# Schaltplan.net
KiCad netlist of a schematic drawn in EAGLE
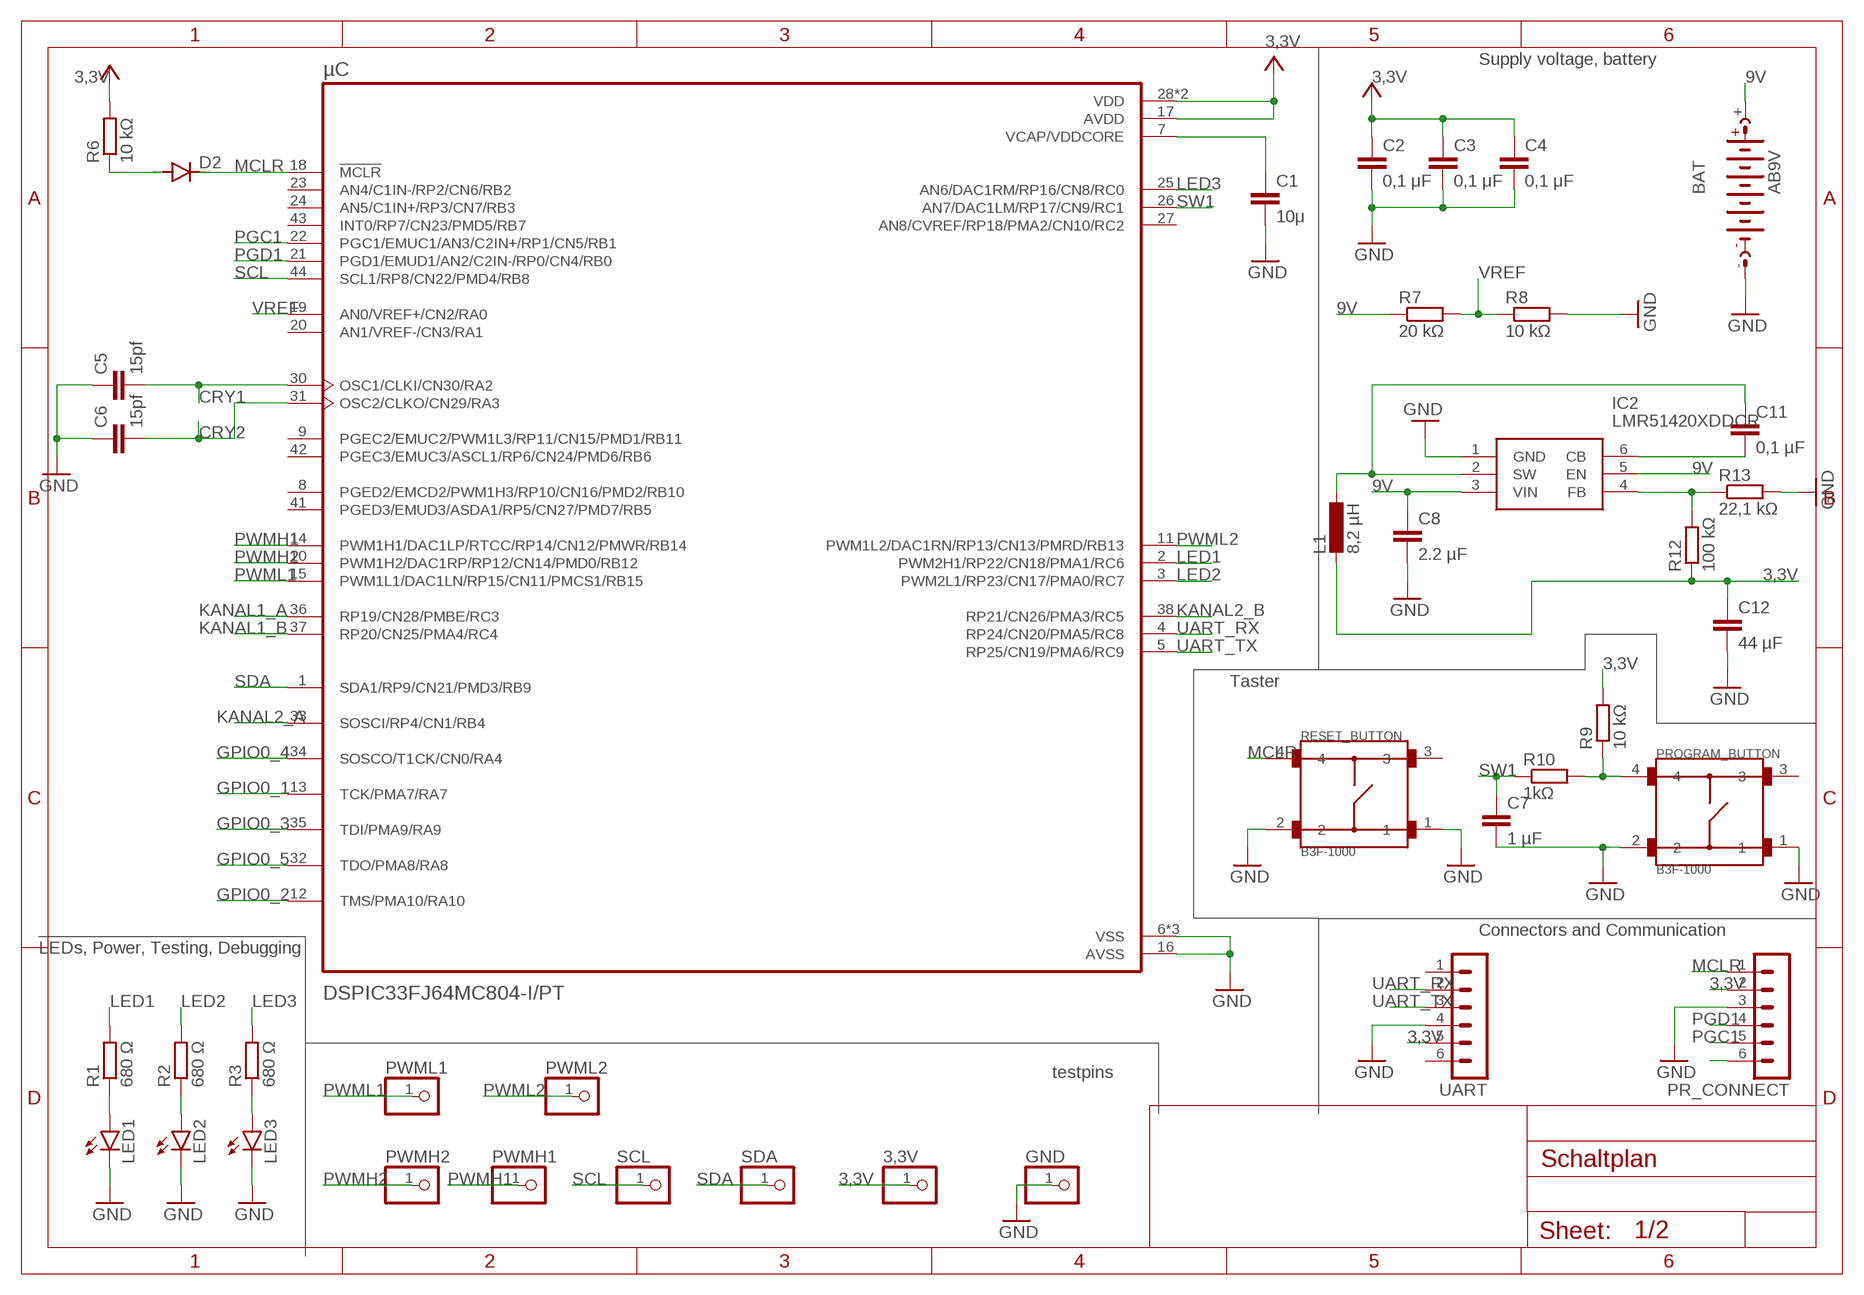
[diagram p0: schematic, sheet 1]
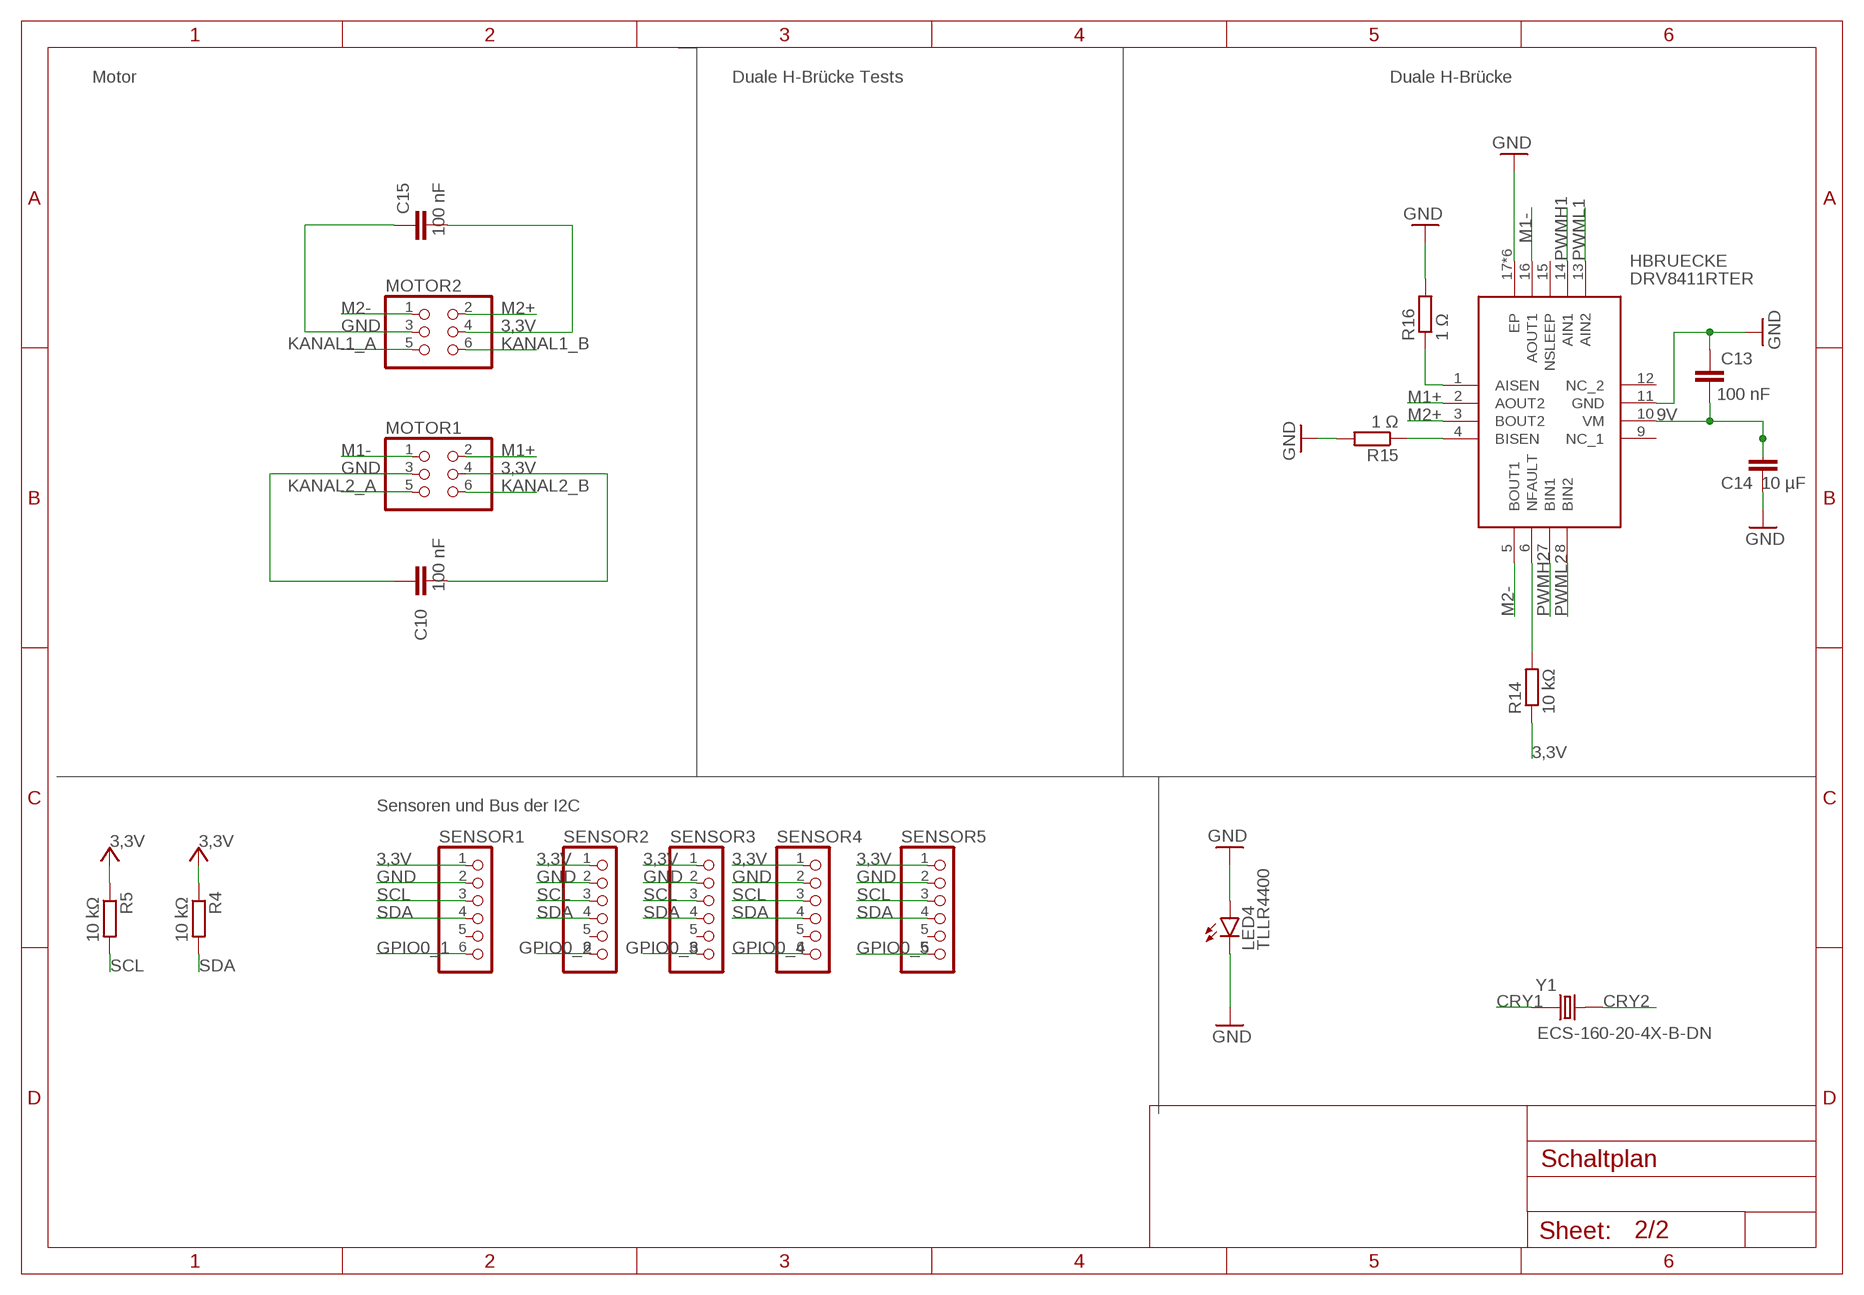
[diagram p1: schematic, sheet 2]

(export (version "E")
  (design (tool "Eeschema 10.0.6"))
  (components
    (comp (ref "3,3V")
      (value "PINHD-1X1")
      (footprint "eagle-import:1X01")
      (libsource (lib "eagle-import") (part "PINHD-1X1"))
    )
    (comp (ref "BAT")
      (value "AB9V")
      (footprint "eagle-import:AB9V")
      (libsource (lib "eagle-import") (part "AB9V"))
    )
    (comp (ref "C1")
      (value "10μ")
      (footprint "eagle-import:C0805")
      (libsource (lib "eagle-import") (part "C-EUC0805"))
    )
    (comp (ref "C2")
      (value "0,1 μF")
      (footprint "eagle-import:C0805")
      (libsource (lib "eagle-import") (part "C-EUC0805"))
    )
    (comp (ref "C3")
      (value "0,1 μF")
      (footprint "eagle-import:C0805")
      (libsource (lib "eagle-import") (part "C-EUC0805"))
    )
    (comp (ref "C4")
      (value "0,1 μF")
      (footprint "eagle-import:C0805")
      (libsource (lib "eagle-import") (part "C-EUC0805"))
    )
    (comp (ref "C5")
      (value "15pf")
      (footprint "eagle-import:C0805")
      (libsource (lib "eagle-import") (part "C-EUC0805"))
    )
    (comp (ref "C6")
      (value "15pf")
      (footprint "eagle-import:C0805")
      (libsource (lib "eagle-import") (part "C-EUC0805"))
    )
    (comp (ref "C7")
      (value "1 µF")
      (footprint "eagle-import:C0805")
      (libsource (lib "eagle-import") (part "C-EUC0805"))
    )
    (comp (ref "C8")
      (value "2.2 µF")
      (footprint "eagle-import:C0805")
      (libsource (lib "eagle-import") (part "C-EUC0805"))
    )
    (comp (ref "C11")
      (value "0,1 µF")
      (footprint "eagle-import:C0805")
      (libsource (lib "eagle-import") (part "C-EUC0805"))
    )
    (comp (ref "C12")
      (value "44 µF")
      (footprint "eagle-import:C0805")
      (libsource (lib "eagle-import") (part "C-EUC0805"))
    )
    (comp (ref "D2")
      (value "DIODE-DO-214AC")
      (footprint "eagle-import:DO-214AC")
      (libsource (lib "eagle-import") (part "DIODE-DO-214AC"))
    )
    (comp (ref "GND")
      (value "PINHD-1X1")
      (footprint "eagle-import:1X01")
      (libsource (lib "eagle-import") (part "PINHD-1X1"))
    )
    (comp (ref "IC2")
      (value "LMR51420XDDCR")
      (footprint "eagle-import:SOT95P280X110-6N")
      (fields (field (name "MOUSER_PART_NUMBER") "595-LMR51420XDDCR"))
      (libsource (lib "eagle-import") (part "LMR51420XDDCR"))
    )
    (comp (ref "L1")
      (value "8,2 µH")
      (footprint "eagle-import:L0201")
      (libsource (lib "eagle-import") (part "L-EUL0201"))
    )
    (comp (ref "LED1")
      (value "LEDCHIPLED_0805")
      (footprint "eagle-import:CHIPLED_0805")
      (libsource (lib "eagle-import") (part "LEDCHIPLED_0805"))
    )
    (comp (ref "LED2")
      (value "LEDCHIPLED_0805")
      (footprint "eagle-import:CHIPLED_0805")
      (libsource (lib "eagle-import") (part "LEDCHIPLED_0805"))
    )
    (comp (ref "LED3")
      (value "LEDCHIPLED_0805")
      (footprint "eagle-import:CHIPLED_0805")
      (libsource (lib "eagle-import") (part "LEDCHIPLED_0805"))
    )
    (comp (ref "PROGRAM_BUTTON")
      (value "B3F-1000")
      (footprint "eagle-import:SW_B3F-1000")
      (fields (field (name "MF") "Omron"))
      (libsource (lib "eagle-import") (part "B3F-1000"))
    )
    (comp (ref "PR_CONNECT")
      (value "MA06-1")
      (footprint "eagle-import:MA06-1")
      (libsource (lib "eagle-import") (part "MA06-1"))
    )
    (comp (ref "PWMH1")
      (value "PINHD-1X1")
      (footprint "eagle-import:1X01")
      (libsource (lib "eagle-import") (part "PINHD-1X1"))
    )
    (comp (ref "PWMH2")
      (value "PINHD-1X1")
      (footprint "eagle-import:1X01")
      (libsource (lib "eagle-import") (part "PINHD-1X1"))
    )
    (comp (ref "PWML1")
      (value "PINHD-1X1")
      (footprint "eagle-import:1X01")
      (libsource (lib "eagle-import") (part "PINHD-1X1"))
    )
    (comp (ref "PWML2")
      (value "PINHD-1X1")
      (footprint "eagle-import:1X01")
      (libsource (lib "eagle-import") (part "PINHD-1X1"))
    )
    (comp (ref "R1")
      (value "680 Ω")
      (footprint "eagle-import:R0805")
      (libsource (lib "eagle-import") (part "R-EU_R0805"))
    )
    (comp (ref "R2")
      (value "680 Ω")
      (footprint "eagle-import:R0805")
      (libsource (lib "eagle-import") (part "R-EU_R0805"))
    )
    (comp (ref "R3")
      (value "680 Ω")
      (footprint "eagle-import:R0805")
      (libsource (lib "eagle-import") (part "R-EU_R0805"))
    )
    (comp (ref "R6")
      (value "10 kΩ")
      (footprint "eagle-import:R0805")
      (libsource (lib "eagle-import") (part "R-EU_R0805"))
    )
    (comp (ref "R7")
      (value "20 kΩ")
      (footprint "eagle-import:R0805")
      (libsource (lib "eagle-import") (part "R-EU_R0805"))
    )
    (comp (ref "R8")
      (value "10 kΩ")
      (footprint "eagle-import:R0805")
      (libsource (lib "eagle-import") (part "R-EU_R0805"))
    )
    (comp (ref "R9")
      (value "10 kΩ")
      (footprint "eagle-import:R0805")
      (libsource (lib "eagle-import") (part "R-EU_R0805"))
    )
    (comp (ref "R10")
      (value "1kΩ")
      (footprint "eagle-import:R0805")
      (libsource (lib "eagle-import") (part "R-EU_R0805"))
    )
    (comp (ref "R12")
      (value "100 kΩ")
      (footprint "eagle-import:R0805")
      (libsource (lib "eagle-import") (part "R-EU_R0805"))
    )
    (comp (ref "R13")
      (value "22,1 kΩ")
      (footprint "eagle-import:R0805")
      (libsource (lib "eagle-import") (part "R-EU_R0805"))
    )
    (comp (ref "RESET_BUTTON")
      (value "B3F-1000")
      (footprint "eagle-import:SW_B3F-1000")
      (fields (field (name "MF") "Omron"))
      (libsource (lib "eagle-import") (part "B3F-1000"))
    )
    (comp (ref "SCL")
      (value "PINHD-1X1")
      (footprint "eagle-import:1X01")
      (libsource (lib "eagle-import") (part "PINHD-1X1"))
    )
    (comp (ref "SDA")
      (value "PINHD-1X1")
      (footprint "eagle-import:1X01")
      (libsource (lib "eagle-import") (part "PINHD-1X1"))
    )
    (comp (ref "UART")
      (value "MA06-1")
      (footprint "eagle-import:MA06-1")
      (libsource (lib "eagle-import") (part "MA06-1"))
    )
    (comp (ref "µC")
      (value "DSPIC33FJ64MC804-I/PT")
      (footprint "eagle-import:QFP80P1200X1200X120-44N")
      (fields (field (name "MF") "Microchip"))
      (libsource (lib "eagle-import") (part "DSPIC33FJ64MC804-I/PT"))
    )
    (comp (ref "C10")
      (value "100 nF")
      (footprint "eagle-import:C0805")
      (libsource (lib "eagle-import") (part "C-EUC0805"))
    )
    (comp (ref "C13")
      (value "100 nF")
      (footprint "eagle-import:C0805")
      (libsource (lib "eagle-import") (part "C-EUC0805"))
    )
    (comp (ref "C14")
      (value "10 µF")
      (footprint "eagle-import:C0805")
      (libsource (lib "eagle-import") (part "C-EUC0805"))
    )
    (comp (ref "C15")
      (value "100 nF")
      (footprint "eagle-import:C0805")
      (libsource (lib "eagle-import") (part "C-EUC0805"))
    )
    (comp (ref "HBRUECKE")
      (value "DRV8411RTER")
      (footprint "eagle-import:QFN50P300X300X80-17N")
      (libsource (lib "eagle-import") (part "DRV8411RTER"))
    )
    (comp (ref "LED4")
      (value "TLLR4400")
      (footprint "eagle-import:LED3MM")
      (fields (field (name "MF") "VISHAY SEMICONDUCTOR"))
      (libsource (lib "eagle-import") (part "TLLR4400"))
    )
    (comp (ref "MOTOR1")
      (value "PINHD-2X3")
      (footprint "eagle-import:2X03")
      (libsource (lib "eagle-import") (part "PINHD-2X3"))
    )
    (comp (ref "MOTOR2")
      (value "PINHD-2X3")
      (footprint "eagle-import:2X03")
      (libsource (lib "eagle-import") (part "PINHD-2X3"))
    )
    (comp (ref "R4")
      (value "10 kΩ")
      (footprint "eagle-import:R0805")
      (libsource (lib "eagle-import") (part "R-EU_R0805"))
    )
    (comp (ref "R5")
      (value "10 kΩ")
      (footprint "eagle-import:R0805")
      (libsource (lib "eagle-import") (part "R-EU_R0805"))
    )
    (comp (ref "R14")
      (value "10 kΩ")
      (footprint "eagle-import:R0805")
      (libsource (lib "eagle-import") (part "R-EU_R0805"))
    )
    (comp (ref "R15")
      (value "1 Ω")
      (footprint "eagle-import:R0805")
      (libsource (lib "eagle-import") (part "R-EU_R0805"))
    )
    (comp (ref "R16")
      (value "1 Ω")
      (footprint "eagle-import:R0805")
      (libsource (lib "eagle-import") (part "R-EU_R0805"))
    )
    (comp (ref "SENSOR1")
      (value "PINHD-1X6")
      (footprint "eagle-import:1X06")
      (libsource (lib "eagle-import") (part "PINHD-1X6"))
    )
    (comp (ref "SENSOR2")
      (value "PINHD-1X6")
      (footprint "eagle-import:1X06")
      (libsource (lib "eagle-import") (part "PINHD-1X6"))
    )
    (comp (ref "SENSOR3")
      (value "PINHD-1X6")
      (footprint "eagle-import:1X06")
      (libsource (lib "eagle-import") (part "PINHD-1X6"))
    )
    (comp (ref "SENSOR4")
      (value "PINHD-1X6")
      (footprint "eagle-import:1X06")
      (libsource (lib "eagle-import") (part "PINHD-1X6"))
    )
    (comp (ref "SENSOR5")
      (value "PINHD-1X6")
      (footprint "eagle-import:1X06")
      (libsource (lib "eagle-import") (part "PINHD-1X6"))
    )
    (comp (ref "Y1")
      (value "ECS-160-20-4X-B-DN")
      (footprint "eagle-import:XTAL_ECS-160-20-4X-B-DN")
      (fields (field (name "MF") "ECS Inc."))
      (libsource (lib "eagle-import") (part "ECS-160-20-4X-B-DN"))
    )
  )
  (nets
    (net (code "1") (name "3,3V") (class "Default")
      (node (ref "3,3V") (pin "1") (pinfunction "1_1") (pintype "passive"))
      (node (ref "C10") (pin "1") (pinfunction "1_1") (pintype "passive"))
      (node (ref "C12") (pin "1") (pinfunction "1_1") (pintype "passive"))
      (node (ref "C15") (pin "1") (pinfunction "1_1") (pintype "passive"))
      (node (ref "C2") (pin "1") (pinfunction "1_1") (pintype "passive"))
      (node (ref "C3") (pin "1") (pinfunction "1_1") (pintype "passive"))
      (node (ref "C4") (pin "1") (pinfunction "1_1") (pintype "passive"))
      (node (ref "L1") (pin "2") (pinfunction "2_2") (pintype "passive"))
      (node (ref "MOTOR1") (pin "4") (pinfunction "4_4") (pintype "passive"))
      (node (ref "MOTOR2") (pin "4") (pinfunction "4_4") (pintype "passive"))
      (node (ref "PR_CONNECT") (pin "2") (pinfunction "2_2") (pintype "passive"))
      (node (ref "R12") (pin "1") (pinfunction "1_1") (pintype "passive"))
      (node (ref "R14") (pin "1") (pinfunction "1_1") (pintype "passive"))
      (node (ref "R4") (pin "1") (pinfunction "1_1") (pintype "passive"))
      (node (ref "R5") (pin "1") (pinfunction "1_1") (pintype "passive"))
      (node (ref "R6") (pin "2") (pinfunction "2_2") (pintype "passive"))
      (node (ref "R9") (pin "2") (pinfunction "2_2") (pintype "passive"))
      (node (ref "SENSOR1") (pin "1") (pinfunction "1_1") (pintype "passive"))
      (node (ref "SENSOR2") (pin "1") (pinfunction "1_1") (pintype "passive"))
      (node (ref "SENSOR3") (pin "1") (pinfunction "1_1") (pintype "passive"))
      (node (ref "SENSOR4") (pin "1") (pinfunction "1_1") (pintype "passive"))
      (node (ref "SENSOR5") (pin "1") (pinfunction "1_1") (pintype "passive"))
      (node (ref "UART") (pin "5") (pinfunction "5_5") (pintype "passive"))
      (node (ref "µC") (pin "17") (pinfunction "AVDD_17") (pintype "power_in"))
      (node (ref "µC") (pin "28") (pinfunction "VDD_28") (pintype "power_in"))
      (node (ref "µC") (pin "40") (pinfunction "VDD_40") (pintype "power_in"))
    )
    (net (code "2") (name "9V") (class "Default")
      (node (ref "BAT") (pin "+") (pinfunction "+_+") (pintype "passive"))
      (node (ref "C13") (pin "1") (pinfunction "1_1") (pintype "passive"))
      (node (ref "C14") (pin "2") (pinfunction "2_2") (pintype "passive"))
      (node (ref "C8") (pin "1") (pinfunction "1_1") (pintype "passive"))
      (node (ref "HBRUECKE") (pin "10") (pinfunction "VM_10") (pintype "bidirectional"))
      (node (ref "IC2") (pin "3") (pinfunction "VIN_3") (pintype "bidirectional"))
      (node (ref "IC2") (pin "5") (pinfunction "EN_5") (pintype "bidirectional"))
      (node (ref "R7") (pin "1") (pinfunction "1_1") (pintype "passive"))
    )
    (net (code "3") (name "CRY1") (class "Default")
      (node (ref "C5") (pin "2") (pinfunction "2_2") (pintype "passive"))
      (node (ref "Y1") (pin "1") (pinfunction "1_1") (pintype "passive"))
      (node (ref "µC") (pin "30") (pinfunction "OSC1/CLKI/CN30/RA2_30") (pintype "bidirectional"))
    )
    (net (code "4") (name "CRY2") (class "Default")
      (node (ref "C6") (pin "2") (pinfunction "2_2") (pintype "passive"))
      (node (ref "Y1") (pin "2") (pinfunction "2_2") (pintype "passive"))
      (node (ref "µC") (pin "31") (pinfunction "OSC2/CLKO/CN29/RA3_31") (pintype "bidirectional"))
    )
    (net (code "5") (name "GND") (class "Default")
      (node (ref "BAT") (pin "-") (pinfunction "-_-") (pintype "passive"))
      (node (ref "C1") (pin "2") (pinfunction "2_2") (pintype "passive"))
      (node (ref "C10") (pin "2") (pinfunction "2_2") (pintype "passive"))
      (node (ref "C12") (pin "2") (pinfunction "2_2") (pintype "passive"))
      (node (ref "C13") (pin "2") (pinfunction "2_2") (pintype "passive"))
      (node (ref "C14") (pin "1") (pinfunction "1_1") (pintype "passive"))
      (node (ref "C15") (pin "2") (pinfunction "2_2") (pintype "passive"))
      (node (ref "C2") (pin "2") (pinfunction "2_2") (pintype "passive"))
      (node (ref "C3") (pin "2") (pinfunction "2_2") (pintype "passive"))
      (node (ref "C4") (pin "2") (pinfunction "2_2") (pintype "passive"))
      (node (ref "C5") (pin "1") (pinfunction "1_1") (pintype "passive"))
      (node (ref "C6") (pin "1") (pinfunction "1_1") (pintype "passive"))
      (node (ref "C7") (pin "2") (pinfunction "2_2") (pintype "passive"))
      (node (ref "C8") (pin "2") (pinfunction "2_2") (pintype "passive"))
      (node (ref "GND") (pin "1") (pinfunction "1_1") (pintype "passive"))
      (node (ref "HBRUECKE") (pin "11") (pinfunction "GND_11") (pintype "bidirectional"))
      (node (ref "HBRUECKE") (pin "17") (pinfunction "EP_17") (pintype "bidirectional"))
      (node (ref "HBRUECKE") (pin "PAD1") (pinfunction "EP_PAD1") (pintype "bidirectional"))
      (node (ref "HBRUECKE") (pin "PAD2") (pinfunction "EP_PAD2") (pintype "bidirectional"))
      (node (ref "HBRUECKE") (pin "PAD3") (pinfunction "EP_PAD3") (pintype "bidirectional"))
      (node (ref "HBRUECKE") (pin "PAD4") (pinfunction "EP_PAD4") (pintype "bidirectional"))
      (node (ref "HBRUECKE") (pin "PAD5") (pinfunction "EP_PAD5") (pintype "bidirectional"))
      (node (ref "IC2") (pin "1") (pinfunction "GND_1") (pintype "bidirectional"))
      (node (ref "LED1") (pin "C") (pinfunction "C_C") (pintype "passive"))
      (node (ref "LED2") (pin "C") (pinfunction "C_C") (pintype "passive"))
      (node (ref "LED3") (pin "C") (pinfunction "C_C") (pintype "passive"))
      (node (ref "LED4") (pin "A") (pinfunction "A_A") (pintype "passive"))
      (node (ref "LED4") (pin "K") (pinfunction "C_K") (pintype "passive"))
      (node (ref "MOTOR1") (pin "3") (pinfunction "3_3") (pintype "passive"))
      (node (ref "MOTOR2") (pin "3") (pinfunction "3_3") (pintype "passive"))
      (node (ref "PROGRAM_BUTTON") (pin "1") (pinfunction "1_1") (pintype "passive"))
      (node (ref "PROGRAM_BUTTON") (pin "2") (pinfunction "2_2") (pintype "passive"))
      (node (ref "PR_CONNECT") (pin "3") (pinfunction "3_3") (pintype "passive"))
      (node (ref "R13") (pin "2") (pinfunction "2_2") (pintype "passive"))
      (node (ref "R15") (pin "2") (pinfunction "2_2") (pintype "passive"))
      (node (ref "R16") (pin "2") (pinfunction "2_2") (pintype "passive"))
      (node (ref "R8") (pin "2") (pinfunction "2_2") (pintype "passive"))
      (node (ref "RESET_BUTTON") (pin "1") (pinfunction "1_1") (pintype "passive"))
      (node (ref "RESET_BUTTON") (pin "2") (pinfunction "2_2") (pintype "passive"))
      (node (ref "SENSOR1") (pin "2") (pinfunction "2_2") (pintype "passive"))
      (node (ref "SENSOR2") (pin "2") (pinfunction "2_2") (pintype "passive"))
      (node (ref "SENSOR3") (pin "2") (pinfunction "2_2") (pintype "passive"))
      (node (ref "SENSOR4") (pin "2") (pinfunction "2_2") (pintype "passive"))
      (node (ref "SENSOR5") (pin "2") (pinfunction "2_2") (pintype "passive"))
      (node (ref "UART") (pin "4") (pinfunction "4_4") (pintype "passive"))
      (node (ref "µC") (pin "16") (pinfunction "AVSS_16") (pintype "power_in"))
      (node (ref "µC") (pin "29") (pinfunction "VSS_29") (pintype "power_in"))
      (node (ref "µC") (pin "39") (pinfunction "VSS_39") (pintype "power_in"))
      (node (ref "µC") (pin "6") (pinfunction "VSS_6") (pintype "power_in"))
    )
    (net (code "6") (name "GPIO0_1") (class "Default")
      (node (ref "SENSOR1") (pin "6") (pinfunction "6_6") (pintype "passive"))
      (node (ref "µC") (pin "13") (pinfunction "TCK/PMA7/RA7_13") (pintype "bidirectional"))
    )
    (net (code "7") (name "GPIO0_2") (class "Default")
      (node (ref "SENSOR2") (pin "6") (pinfunction "6_6") (pintype "passive"))
      (node (ref "µC") (pin "12") (pinfunction "TMS/PMA10/RA10_12") (pintype "bidirectional"))
    )
    (net (code "8") (name "GPIO0_3") (class "Default")
      (node (ref "SENSOR3") (pin "6") (pinfunction "6_6") (pintype "passive"))
      (node (ref "µC") (pin "35") (pinfunction "TDI/PMA9/RA9_35") (pintype "bidirectional"))
    )
    (net (code "9") (name "GPIO0_4") (class "Default")
      (node (ref "SENSOR4") (pin "6") (pinfunction "6_6") (pintype "passive"))
      (node (ref "µC") (pin "34") (pinfunction "SOSCO/T1CK/CN0/RA4_34") (pintype "bidirectional"))
    )
    (net (code "10") (name "GPIO0_5") (class "Default")
      (node (ref "SENSOR5") (pin "6") (pinfunction "6_6") (pintype "passive"))
      (node (ref "µC") (pin "32") (pinfunction "TDO/PMA8/RA8_32") (pintype "bidirectional"))
    )
    (net (code "11") (name "KANAL1_A") (class "Default")
      (node (ref "MOTOR2") (pin "5") (pinfunction "5_5") (pintype "passive"))
      (node (ref "µC") (pin "36") (pinfunction "RP19/CN28/PMBE/RC3_36") (pintype "bidirectional"))
    )
    (net (code "12") (name "KANAL1_B") (class "Default")
      (node (ref "MOTOR2") (pin "6") (pinfunction "6_6") (pintype "passive"))
      (node (ref "µC") (pin "37") (pinfunction "RP20/CN25/PMA4/RC4_37") (pintype "bidirectional"))
    )
    (net (code "13") (name "KANAL2_A") (class "Default")
      (node (ref "MOTOR1") (pin "5") (pinfunction "5_5") (pintype "passive"))
      (node (ref "µC") (pin "33") (pinfunction "SOSCI/RP4/CN1/RB4_33") (pintype "bidirectional"))
    )
    (net (code "14") (name "KANAL2_B") (class "Default")
      (node (ref "MOTOR1") (pin "6") (pinfunction "6_6") (pintype "passive"))
      (node (ref "µC") (pin "38") (pinfunction "RP21/CN26/PMA3/RC5_38") (pintype "bidirectional"))
    )
    (net (code "15") (name "LED1") (class "Default")
      (node (ref "R1") (pin "2") (pinfunction "2_2") (pintype "passive"))
      (node (ref "µC") (pin "2") (pinfunction "PWM2H1/RP22/CN18/PMA1/RC6_2") (pintype "bidirectional"))
    )
    (net (code "16") (name "LED2") (class "Default")
      (node (ref "R2") (pin "2") (pinfunction "2_2") (pintype "passive"))
      (node (ref "µC") (pin "3") (pinfunction "PWM2L1/RP23/CN17/PMA0/RC7_3") (pintype "bidirectional"))
    )
    (net (code "17") (name "LED3") (class "Default")
      (node (ref "R3") (pin "2") (pinfunction "2_2") (pintype "passive"))
      (node (ref "µC") (pin "25") (pinfunction "AN6/DAC1RM/RP16/CN8/RC0_25") (pintype "bidirectional"))
    )
    (net (code "18") (name "M1+") (class "Default")
      (node (ref "HBRUECKE") (pin "2") (pinfunction "AOUT2_2") (pintype "bidirectional"))
      (node (ref "MOTOR1") (pin "2") (pinfunction "2_2") (pintype "passive"))
    )
    (net (code "19") (name "M1-") (class "Default")
      (node (ref "HBRUECKE") (pin "16") (pinfunction "AOUT1_16") (pintype "bidirectional"))
      (node (ref "MOTOR1") (pin "1") (pinfunction "1_1") (pintype "passive"))
    )
    (net (code "20") (name "M2+") (class "Default")
      (node (ref "HBRUECKE") (pin "3") (pinfunction "BOUT2_3") (pintype "bidirectional"))
      (node (ref "MOTOR2") (pin "2") (pinfunction "2_2") (pintype "passive"))
    )
    (net (code "21") (name "M2-") (class "Default")
      (node (ref "HBRUECKE") (pin "5") (pinfunction "BOUT1_5") (pintype "bidirectional"))
      (node (ref "MOTOR2") (pin "1") (pinfunction "1_1") (pintype "passive"))
    )
    (net (code "22") (name "MCLR") (class "Default")
      (node (ref "D2") (pin "C") (pinfunction "C_C") (pintype "passive"))
      (node (ref "PR_CONNECT") (pin "1") (pinfunction "1_1") (pintype "passive"))
      (node (ref "RESET_BUTTON") (pin "4") (pinfunction "4_4") (pintype "passive"))
      (node (ref "µC") (pin "18") (pinfunction "~{MCLR}_18") (pintype "input"))
    )
    (net (code "23") (name "Net-(D2-PadA)") (class "Default")
      (node (ref "D2") (pin "A") (pinfunction "A_A") (pintype "passive"))
      (node (ref "R6") (pin "1") (pinfunction "1_1") (pintype "passive"))
    )
    (net (code "24") (name "Net-(HBRUECKE-AISEN)") (class "Default")
      (node (ref "HBRUECKE") (pin "1") (pinfunction "AISEN_1") (pintype "bidirectional"))
      (node (ref "R16") (pin "1") (pinfunction "1_1") (pintype "passive"))
    )
    (net (code "25") (name "Net-(HBRUECKE-BISEN)") (class "Default")
      (node (ref "HBRUECKE") (pin "4") (pinfunction "BISEN_4") (pintype "bidirectional"))
      (node (ref "R15") (pin "1") (pinfunction "1_1") (pintype "passive"))
    )
    (net (code "26") (name "Net-(HBRUECKE-NFAULT)") (class "Default")
      (node (ref "HBRUECKE") (pin "6") (pinfunction "NFAULT_6") (pintype "bidirectional"))
      (node (ref "R14") (pin "2") (pinfunction "2_2") (pintype "passive"))
    )
    (net (code "27") (name "Net-(IC2-CB)") (class "Default")
      (node (ref "C11") (pin "2") (pinfunction "2_2") (pintype "passive"))
      (node (ref "IC2") (pin "6") (pinfunction "CB_6") (pintype "bidirectional"))
    )
    (net (code "28") (name "Net-(IC2-FB)") (class "Default")
      (node (ref "IC2") (pin "4") (pinfunction "FB_4") (pintype "bidirectional"))
      (node (ref "R12") (pin "2") (pinfunction "2_2") (pintype "passive"))
      (node (ref "R13") (pin "1") (pinfunction "1_1") (pintype "passive"))
    )
    (net (code "29") (name "Net-(IC2-SW)") (class "Default")
      (node (ref "C11") (pin "1") (pinfunction "1_1") (pintype "passive"))
      (node (ref "IC2") (pin "2") (pinfunction "SW_2") (pintype "bidirectional"))
      (node (ref "L1") (pin "1") (pinfunction "1_1") (pintype "passive"))
    )
    (net (code "30") (name "Net-(LED1-PadA)") (class "Default")
      (node (ref "LED1") (pin "A") (pinfunction "A_A") (pintype "passive"))
      (node (ref "R1") (pin "1") (pinfunction "1_1") (pintype "passive"))
    )
    (net (code "31") (name "Net-(LED2-PadA)") (class "Default")
      (node (ref "LED2") (pin "A") (pinfunction "A_A") (pintype "passive"))
      (node (ref "R2") (pin "1") (pinfunction "1_1") (pintype "passive"))
    )
    (net (code "32") (name "Net-(LED3-PadA)") (class "Default")
      (node (ref "LED3") (pin "A") (pinfunction "A_A") (pintype "passive"))
      (node (ref "R3") (pin "1") (pinfunction "1_1") (pintype "passive"))
    )
    (net (code "33") (name "Net-(PROGRAM_BUTTON-Pad4)") (class "Default")
      (node (ref "PROGRAM_BUTTON") (pin "4") (pinfunction "4_4") (pintype "passive"))
      (node (ref "R10") (pin "2") (pinfunction "2_2") (pintype "passive"))
      (node (ref "R9") (pin "1") (pinfunction "1_1") (pintype "passive"))
    )
    (net (code "34") (name "Net-(µC-VCAP{slash}VDDCORE)") (class "Default")
      (node (ref "C1") (pin "1") (pinfunction "1_1") (pintype "passive"))
      (node (ref "µC") (pin "7") (pinfunction "VCAP/VDDCORE_7") (pintype "power_in"))
    )
    (net (code "35") (name "PGC1") (class "Default")
      (node (ref "PR_CONNECT") (pin "5") (pinfunction "5_5") (pintype "passive"))
      (node (ref "µC") (pin "22") (pinfunction "PGC1/EMUC1/AN3/C2IN+/RP1/CN5/RB1_22") (pintype "input"))
    )
    (net (code "36") (name "PGD1") (class "Default")
      (node (ref "PR_CONNECT") (pin "4") (pinfunction "4_4") (pintype "passive"))
      (node (ref "µC") (pin "21") (pinfunction "PGD1/EMUD1/AN2/C2IN-/RP0/CN4/RB0_21") (pintype "input"))
    )
    (net (code "37") (name "PWMH1") (class "Default")
      (node (ref "HBRUECKE") (pin "14") (pinfunction "AIN1_14") (pintype "bidirectional"))
      (node (ref "PWMH1") (pin "1") (pinfunction "1_1") (pintype "passive"))
      (node (ref "µC") (pin "14") (pinfunction "PWM1H1/DAC1LP/RTCC/RP14/CN12/PMWR/RB14_14") (pintype "bidirectional"))
    )
    (net (code "38") (name "PWMH2") (class "Default")
      (node (ref "HBRUECKE") (pin "7") (pinfunction "BIN1_7") (pintype "bidirectional"))
      (node (ref "PWMH2") (pin "1") (pinfunction "1_1") (pintype "passive"))
      (node (ref "µC") (pin "10") (pinfunction "PWM1H2/DAC1RP/RP12/CN14/PMD0/RB12_10") (pintype "bidirectional"))
    )
    (net (code "39") (name "PWML1") (class "Default")
      (node (ref "HBRUECKE") (pin "13") (pinfunction "AIN2_13") (pintype "bidirectional"))
      (node (ref "PWML1") (pin "1") (pinfunction "1_1") (pintype "passive"))
      (node (ref "µC") (pin "15") (pinfunction "PWM1L1/DAC1LN/RP15/CN11/PMCS1/RB15_15") (pintype "bidirectional"))
    )
    (net (code "40") (name "PWML2") (class "Default")
      (node (ref "HBRUECKE") (pin "8") (pinfunction "BIN2_8") (pintype "bidirectional"))
      (node (ref "PWML2") (pin "1") (pinfunction "1_1") (pintype "passive"))
      (node (ref "µC") (pin "11") (pinfunction "PWM1L2/DAC1RN/RP13/CN13/PMRD/RB13_11") (pintype "bidirectional"))
    )
    (net (code "41") (name "SCL") (class "Default")
      (node (ref "R5") (pin "2") (pinfunction "2_2") (pintype "passive"))
      (node (ref "SCL") (pin "1") (pinfunction "1_1") (pintype "passive"))
      (node (ref "SENSOR1") (pin "3") (pinfunction "3_3") (pintype "passive"))
      (node (ref "SENSOR2") (pin "3") (pinfunction "3_3") (pintype "passive"))
      (node (ref "SENSOR3") (pin "3") (pinfunction "3_3") (pintype "passive"))
      (node (ref "SENSOR4") (pin "3") (pinfunction "3_3") (pintype "passive"))
      (node (ref "SENSOR5") (pin "3") (pinfunction "3_3") (pintype "passive"))
      (node (ref "µC") (pin "44") (pinfunction "SCL1/RP8/CN22/PMD4/RB8_44") (pintype "input"))
    )
    (net (code "42") (name "SDA") (class "Default")
      (node (ref "R4") (pin "2") (pinfunction "2_2") (pintype "passive"))
      (node (ref "SDA") (pin "1") (pinfunction "1_1") (pintype "passive"))
      (node (ref "SENSOR1") (pin "4") (pinfunction "4_4") (pintype "passive"))
      (node (ref "SENSOR2") (pin "4") (pinfunction "4_4") (pintype "passive"))
      (node (ref "SENSOR3") (pin "4") (pinfunction "4_4") (pintype "passive"))
      (node (ref "SENSOR4") (pin "4") (pinfunction "4_4") (pintype "passive"))
      (node (ref "SENSOR5") (pin "4") (pinfunction "4_4") (pintype "passive"))
      (node (ref "µC") (pin "1") (pinfunction "SDA1/RP9/CN21/PMD3/RB9_1") (pintype "bidirectional"))
    )
    (net (code "43") (name "SW1") (class "Default")
      (node (ref "C7") (pin "1") (pinfunction "1_1") (pintype "passive"))
      (node (ref "R10") (pin "1") (pinfunction "1_1") (pintype "passive"))
      (node (ref "µC") (pin "26") (pinfunction "AN7/DAC1LM/RP17/CN9/RC1_26") (pintype "bidirectional"))
    )
    (net (code "44") (name "UART_RX") (class "Default")
      (node (ref "UART") (pin "2") (pinfunction "2_2") (pintype "passive"))
      (node (ref "µC") (pin "4") (pinfunction "RP24/CN20/PMA5/RC8_4") (pintype "bidirectional"))
    )
    (net (code "45") (name "UART_TX") (class "Default")
      (node (ref "UART") (pin "3") (pinfunction "3_3") (pintype "passive"))
      (node (ref "µC") (pin "5") (pinfunction "RP25/CN19/PMA6/RC9_5") (pintype "bidirectional"))
    )
    (net (code "46") (name "VREF") (class "Default")
      (node (ref "R7") (pin "2") (pinfunction "2_2") (pintype "passive"))
      (node (ref "R8") (pin "1") (pinfunction "1_1") (pintype "passive"))
      (node (ref "µC") (pin "19") (pinfunction "AN0/VREF+/CN2/RA0_19") (pintype "bidirectional"))
    )
    (net (code "47") (name "unconnected-(HBRUECKE-NC_1-Pad9)") (class "Default")
      (node (ref "HBRUECKE") (pin "9") (pinfunction "NC_1_9") (pintype "bidirectional"))
    )
    (net (code "48") (name "unconnected-(HBRUECKE-NC_2-Pad12)") (class "Default")
      (node (ref "HBRUECKE") (pin "12") (pinfunction "NC_2_12") (pintype "bidirectional"))
    )
    (net (code "49") (name "unconnected-(HBRUECKE-NSLEEP-Pad15)") (class "Default")
      (node (ref "HBRUECKE") (pin "15") (pinfunction "NSLEEP_15") (pintype "bidirectional"))
    )
    (net (code "50") (name "unconnected-(PROGRAM_BUTTON-Pad3)") (class "Default")
      (node (ref "PROGRAM_BUTTON") (pin "3") (pinfunction "3_3") (pintype "passive"))
    )
    (net (code "51") (name "unconnected-(PR_CONNECT-Pad6)") (class "Default")
      (node (ref "PR_CONNECT") (pin "6") (pinfunction "6_6") (pintype "passive"))
    )
    (net (code "52") (name "unconnected-(RESET_BUTTON-Pad3)") (class "Default")
      (node (ref "RESET_BUTTON") (pin "3") (pinfunction "3_3") (pintype "passive"))
    )
    (net (code "53") (name "unconnected-(SENSOR1-Pad5)") (class "Default")
      (node (ref "SENSOR1") (pin "5") (pinfunction "5_5") (pintype "passive"))
    )
    (net (code "54") (name "unconnected-(SENSOR2-Pad5)") (class "Default")
      (node (ref "SENSOR2") (pin "5") (pinfunction "5_5") (pintype "passive"))
    )
    (net (code "55") (name "unconnected-(SENSOR3-Pad5)") (class "Default")
      (node (ref "SENSOR3") (pin "5") (pinfunction "5_5") (pintype "passive"))
    )
    (net (code "56") (name "unconnected-(SENSOR4-Pad5)") (class "Default")
      (node (ref "SENSOR4") (pin "5") (pinfunction "5_5") (pintype "passive"))
    )
    (net (code "57") (name "unconnected-(SENSOR5-Pad5)") (class "Default")
      (node (ref "SENSOR5") (pin "5") (pinfunction "5_5") (pintype "passive"))
    )
    (net (code "58") (name "unconnected-(UART-Pad1)") (class "Default")
      (node (ref "UART") (pin "1") (pinfunction "1_1") (pintype "passive"))
    )
    (net (code "59") (name "unconnected-(UART-Pad6)") (class "Default")
      (node (ref "UART") (pin "6") (pinfunction "6_6") (pintype "passive"))
    )
    (net (code "60") (name "unconnected-(µC-AN1{slash}VREF-{slash}CN3{slash}RA1-Pad20)") (class "Default")
      (node (ref "µC") (pin "20") (pinfunction "AN1/VREF-/CN3/RA1_20") (pintype "bidirectional"))
    )
    (net (code "61") (name "unconnected-(µC-AN4{slash}C1IN-{slash}RP2{slash}CN6{slash}RB2-Pad23)") (class "Default")
      (node (ref "µC") (pin "23") (pinfunction "AN4/C1IN-/RP2/CN6/RB2_23") (pintype "input"))
    )
    (net (code "62") (name "unconnected-(µC-AN5{slash}C1IN+{slash}RP3{slash}CN7{slash}RB3-Pad24)") (class "Default")
      (node (ref "µC") (pin "24") (pinfunction "AN5/C1IN+/RP3/CN7/RB3_24") (pintype "input"))
    )
    (net (code "63") (name "unconnected-(µC-AN8{slash}CVREF{slash}RP18{slash}PMA2{slash}CN10{slash}RC2-Pad27)") (class "Default")
      (node (ref "µC") (pin "27") (pinfunction "AN8/CVREF/RP18/PMA2/CN10/RC2_27") (pintype "bidirectional"))
    )
    (net (code "64") (name "unconnected-(µC-INT0{slash}RP7{slash}CN23{slash}PMD5{slash}RB7-Pad43)") (class "Default")
      (node (ref "µC") (pin "43") (pinfunction "INT0/RP7/CN23/PMD5/RB7_43") (pintype "input"))
    )
    (net (code "65") (name "unconnected-(µC-PGEC2{slash}EMUC2{slash}PWM1L3{slash}RP11{slash}CN15{slash}PMD1{slash}RB11-Pad9)") (class "Default")
      (node (ref "µC") (pin "9") (pinfunction "PGEC2/EMUC2/PWM1L3/RP11/CN15/PMD1/RB11_9") (pintype "bidirectional"))
    )
    (net (code "66") (name "unconnected-(µC-PGEC3{slash}EMUC3{slash}ASCL1{slash}RP6{slash}CN24{slash}PMD6{slash}RB6-Pad42)") (class "Default")
      (node (ref "µC") (pin "42") (pinfunction "PGEC3/EMUC3/ASCL1/RP6/CN24/PMD6/RB6_42") (pintype "bidirectional"))
    )
    (net (code "67") (name "unconnected-(µC-PGED2{slash}EMCD2{slash}PWM1H3{slash}RP10{slash}CN16{slash}PMD2{slash}RB10-Pad8)") (class "Default")
      (node (ref "µC") (pin "8") (pinfunction "PGED2/EMCD2/PWM1H3/RP10/CN16/PMD2/RB10_8") (pintype "bidirectional"))
    )
    (net (code "68") (name "unconnected-(µC-PGED3{slash}EMUD3{slash}ASDA1{slash}RP5{slash}CN27{slash}PMD7{slash}RB5-Pad41)") (class "Default")
      (node (ref "µC") (pin "41") (pinfunction "PGED3/EMUD3/ASDA1/RP5/CN27/PMD7/RB5_41") (pintype "bidirectional"))
    )
  )
)
